# v2_6_Schematic.net
KiCad netlist of a schematic drawn in EAGLE
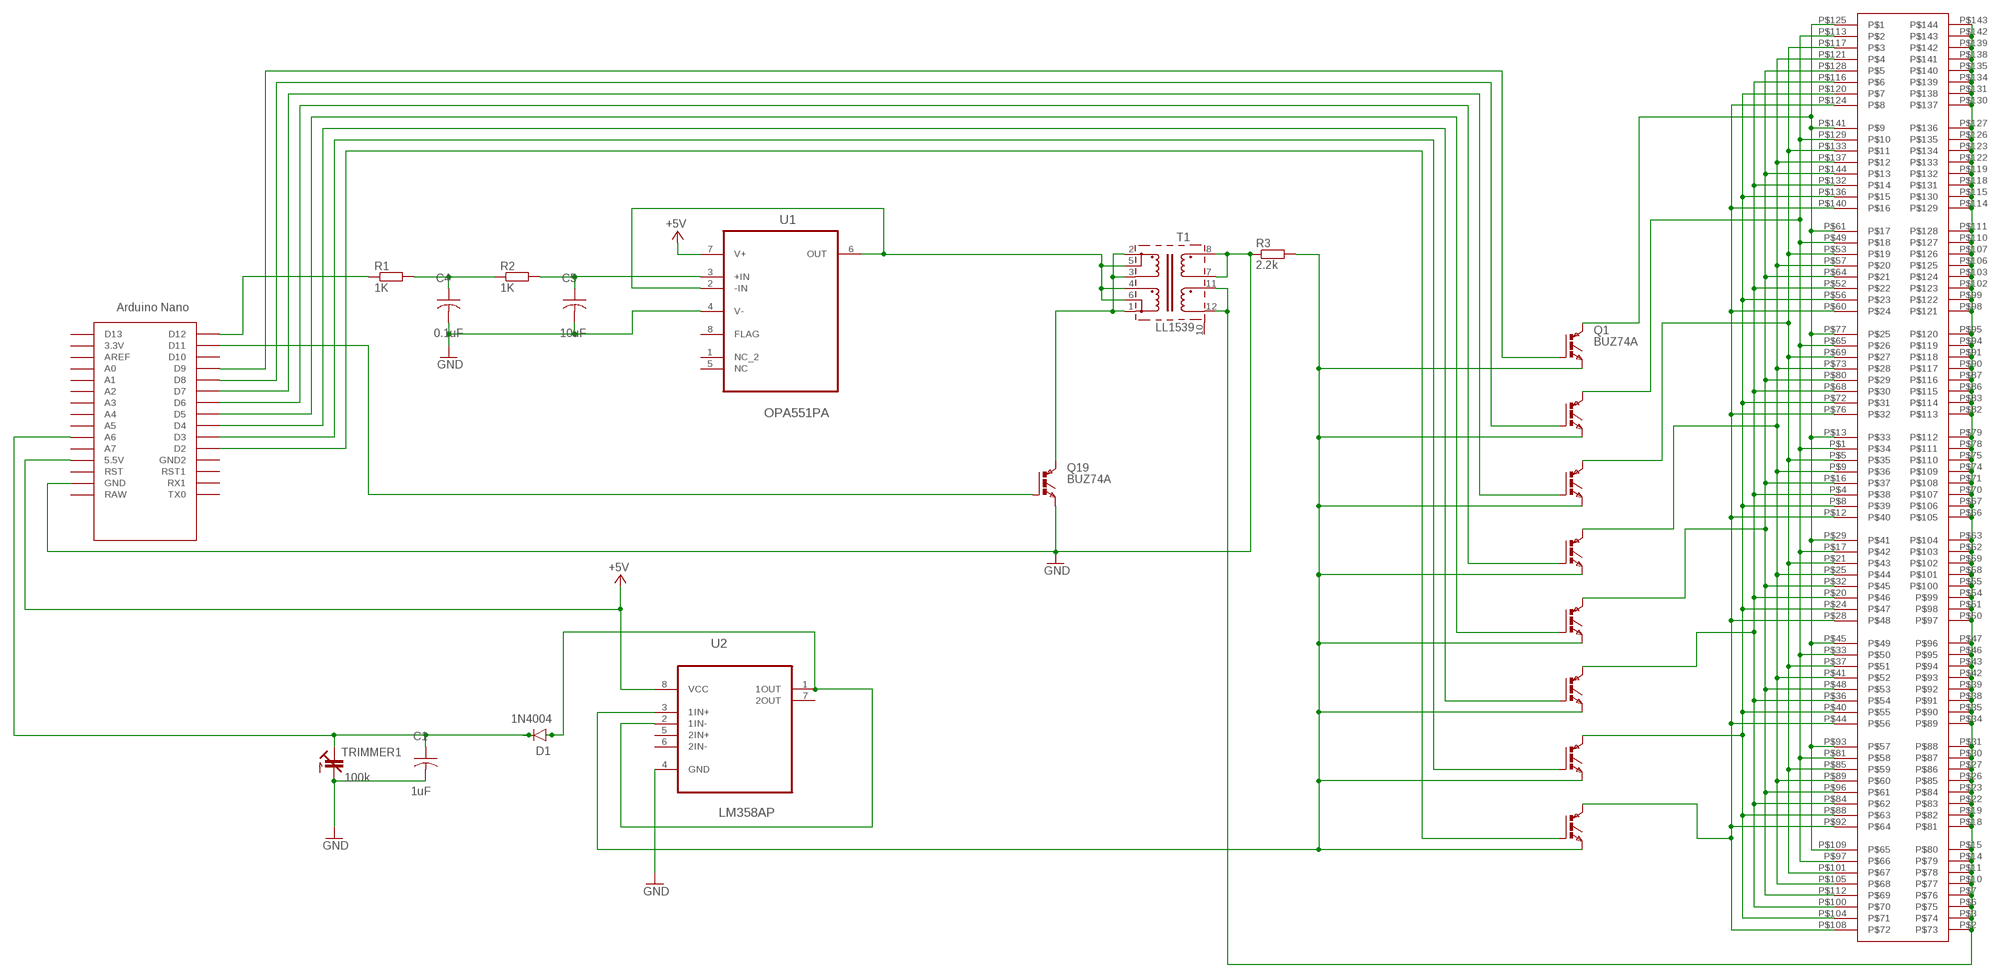
[diagram p0: schematic, sheet 1]

(export (version "E")
  (design (tool "Eeschema 10.0.6"))
  (components
    (comp (ref "C1")
      (value "1uF")
      (footprint "eagle-import:CAP_RADIAL_2MM")
      (fields
        (field (name "DIGIKEY_PART_NUMBER") "P5178-ND")
        (field (name "MANUFACTURER") "Panasonic Electronic Components")
        (field (name "MPN") "ECA-1HM100")
        (field (name "CREATED_BY") "PCBLayout.com")
      )
      (libsource (lib "eagle-import") (part "ECA-1HM100"))
    )
    (comp (ref "C4")
      (value "0.1uF")
      (footprint "eagle-import:CAP_RADIAL_2MM")
      (fields
        (field (name "DIGIKEY_PART_NUMBER") "P5178-ND")
        (field (name "MANUFACTURER") "Panasonic Electronic Components")
        (field (name "MPN") "ECA-1HM100")
        (field (name "CREATED_BY") "PCBLayout.com")
      )
      (libsource (lib "eagle-import") (part "ECA-1HM100"))
    )
    (comp (ref "C5")
      (value "10uF")
      (footprint "eagle-import:CAP_RADIAL_2MM")
      (fields
        (field (name "DIGIKEY_PART_NUMBER") "P5178-ND")
        (field (name "MANUFACTURER") "Panasonic Electronic Components")
        (field (name "MPN") "ECA-1HM100")
        (field (name "CREATED_BY") "PCBLayout.com")
      )
      (libsource (lib "eagle-import") (part "ECA-1HM100"))
    )
    (comp (ref "D1")
      (value "1N4004")
      (footprint "eagle-import:DO-41")
      (fields
        (field (name "DIGIKEY_PART_NUMBER") "1N4004MSCT-ND")
        (field (name "MANUFACTURER") "Micro Commercial Co")
        (field (name "CREATED_BY") "PCBLayout.com")
      )
      (libsource (lib "eagle-import") (part "1N4004"))
    )
    (comp (ref "Q1")
      (value "BUZ74A")
      (footprint "eagle-import:TO220AV")
      (libsource (lib "eagle-import") (part "IGBTTO220AV"))
    )
    (comp (ref "Q2")
      (value "BUZ74A")
      (footprint "eagle-import:TO220AV")
      (libsource (lib "eagle-import") (part "IGBTTO220AV"))
    )
    (comp (ref "Q3")
      (value "BUZ74A")
      (footprint "eagle-import:TO220AV")
      (libsource (lib "eagle-import") (part "IGBTTO220AV"))
    )
    (comp (ref "Q4")
      (value "BUZ74A")
      (footprint "eagle-import:TO220AV")
      (libsource (lib "eagle-import") (part "IGBTTO220AV"))
    )
    (comp (ref "Q5")
      (value "BUZ74A")
      (footprint "eagle-import:TO220AV")
      (libsource (lib "eagle-import") (part "IGBTTO220AV"))
    )
    (comp (ref "Q6")
      (value "BUZ74A")
      (footprint "eagle-import:TO220AV")
      (libsource (lib "eagle-import") (part "IGBTTO220AV"))
    )
    (comp (ref "Q7")
      (value "BUZ74A")
      (footprint "eagle-import:TO220AV")
      (libsource (lib "eagle-import") (part "IGBTTO220AV"))
    )
    (comp (ref "Q8")
      (value "BUZ74A")
      (footprint "eagle-import:TO220AV")
      (libsource (lib "eagle-import") (part "IGBTTO220AV"))
    )
    (comp (ref "Q19")
      (value "BUZ74A")
      (footprint "eagle-import:TO220AV")
      (libsource (lib "eagle-import") (part "IGBTTO220AV"))
    )
    (comp (ref "R1")
      (value "1K")
      (footprint "eagle-import:0204V")
      (libsource (lib "eagle-import") (part "R-EU_0204/2V"))
    )
    (comp (ref "R2")
      (value "1K")
      (footprint "eagle-import:0204V")
      (libsource (lib "eagle-import") (part "R-EU_0204/2V"))
    )
    (comp (ref "R3")
      (value "2.2k")
      (footprint "eagle-import:0204V")
      (libsource (lib "eagle-import") (part "R-EU_0204/2V"))
    )
    (comp (ref "T1")
      (value "LL1539")
      (footprint "eagle-import:LL1539")
      (libsource (lib "eagle-import") (part "LL1539"))
    )
    (comp (ref "TRIMMER1")
      (value "100k")
      (footprint "eagle-import:CTRIM3040.452")
      (libsource (lib "eagle-import") (part "C-TRIMM3040.452"))
    )
    (comp (ref "U$1")
      (value "NANO")
      (footprint "eagle-import:NANO")
      (libsource (lib "eagle-import") (part "NANO"))
    )
    (comp (ref "U$2")
      (value "DOTS_V2")
      (footprint "eagle-import:DOTS_V2")
      (libsource (lib "eagle-import") (part "DOTS_V2"))
    )
    (comp (ref "U1")
      (value "OPA551PA")
      (footprint "eagle-import:DIP254P762X508-8")
      (libsource (lib "eagle-import") (part "OPA551PA"))
    )
    (comp (ref "U2")
      (value "LM358AP")
      (footprint "eagle-import:DIP254P762X508-8")
      (libsource (lib "eagle-import") (part "LM358AP"))
    )
  )
  (nets
    (net (code "1") (name "+5V") (class "Default")
      (node (ref "U$1") (pin "5V") (pinfunction "5.5V_5V") (pintype "bidirectional"))
      (node (ref "U1") (pin "7") (pinfunction "V+_7") (pintype "power_in"))
      (node (ref "U2") (pin "8") (pinfunction "VCC_8") (pintype "power_in"))
    )
    (net (code "2") (name "GND") (class "Default")
      (node (ref "C1") (pin "2") (pinfunction "2_2") (pintype "passive"))
      (node (ref "C4") (pin "2") (pinfunction "2_2") (pintype "passive"))
      (node (ref "C5") (pin "2") (pinfunction "2_2") (pintype "passive"))
      (node (ref "Q19") (pin "E") (pinfunction "E_E") (pintype "passive"))
      (node (ref "R3") (pin "1") (pinfunction "1_1") (pintype "passive"))
      (node (ref "T1") (pin "7") (pinfunction "7_7") (pintype "passive"))
      (node (ref "T1") (pin "8") (pinfunction "8_8") (pintype "passive"))
      (node (ref "TRIMMER1") (pin "2") (pinfunction "A_2") (pintype "passive"))
      (node (ref "U$1") (pin "GND") (pinfunction "GND_GND") (pintype "bidirectional"))
      (node (ref "U1") (pin "4") (pinfunction "V-_4") (pintype "power_in"))
      (node (ref "U2") (pin "4") (pinfunction "GND_4") (pintype "passive"))
    )
    (net (code "3") (name "Net-(C4-Pad1)") (class "Default")
      (node (ref "C4") (pin "1") (pinfunction "1_1") (pintype "passive"))
      (node (ref "R1") (pin "2") (pinfunction "2_2") (pintype "passive"))
      (node (ref "R2") (pin "1") (pinfunction "1_1") (pintype "passive"))
    )
    (net (code "4") (name "Net-(Q1-PadG)") (class "Default")
      (node (ref "Q1") (pin "G") (pinfunction "G_G") (pintype "passive"))
      (node (ref "U$1") (pin "D9") (pinfunction "D9_D9") (pintype "bidirectional"))
    )
    (net (code "5") (name "Net-(Q2-PadG)") (class "Default")
      (node (ref "Q2") (pin "G") (pinfunction "G_G") (pintype "passive"))
      (node (ref "U$1") (pin "D8") (pinfunction "D8_D8") (pintype "bidirectional"))
    )
    (net (code "6") (name "Net-(Q3-PadG)") (class "Default")
      (node (ref "Q3") (pin "G") (pinfunction "G_G") (pintype "passive"))
      (node (ref "U$1") (pin "D7") (pinfunction "D7_D7") (pintype "bidirectional"))
    )
    (net (code "7") (name "Net-(Q4-PadG)") (class "Default")
      (node (ref "Q4") (pin "G") (pinfunction "G_G") (pintype "passive"))
      (node (ref "U$1") (pin "D6") (pinfunction "D6_D6") (pintype "bidirectional"))
    )
    (net (code "8") (name "Net-(Q5-PadG)") (class "Default")
      (node (ref "Q5") (pin "G") (pinfunction "G_G") (pintype "passive"))
      (node (ref "U$1") (pin "D5") (pinfunction "D5_D5") (pintype "bidirectional"))
    )
    (net (code "9") (name "Net-(Q6-PadG)") (class "Default")
      (node (ref "Q6") (pin "G") (pinfunction "G_G") (pintype "passive"))
      (node (ref "U$1") (pin "D4") (pinfunction "D4_D4") (pintype "bidirectional"))
    )
    (net (code "10") (name "Net-(Q7-PadG)") (class "Default")
      (node (ref "Q7") (pin "G") (pinfunction "G_G") (pintype "passive"))
      (node (ref "U$1") (pin "D3") (pinfunction "D3_D3") (pintype "bidirectional"))
    )
    (net (code "11") (name "Net-(Q8-PadG)") (class "Default")
      (node (ref "Q8") (pin "G") (pinfunction "G_G") (pintype "passive"))
      (node (ref "U$1") (pin "D2") (pinfunction "D2_D2") (pintype "bidirectional"))
    )
    (net (code "12") (name "Net-(Q19-PadC)") (class "Default")
      (node (ref "Q19") (pin "C") (pinfunction "C_C") (pintype "passive"))
      (node (ref "T1") (pin "1") (pinfunction "1_1") (pintype "passive"))
      (node (ref "T1") (pin "2") (pinfunction "2_2") (pintype "passive"))
      (node (ref "T1") (pin "3") (pinfunction "3_3") (pintype "passive"))
    )
    (net (code "13") (name "Net-(Q19-PadG)") (class "Default")
      (node (ref "Q19") (pin "G") (pinfunction "G_G") (pintype "passive"))
      (node (ref "U$1") (pin "D11") (pinfunction "D11_D11") (pintype "bidirectional"))
    )
    (net (code "14") (name "Net-(R1-Pad1)") (class "Default")
      (node (ref "R1") (pin "1") (pinfunction "1_1") (pintype "passive"))
      (node (ref "U$1") (pin "D12") (pinfunction "D12_D12") (pintype "bidirectional"))
    )
    (net (code "15") (name "Net-(TRIMMER1-E)") (class "Default")
      (node (ref "C1") (pin "1") (pinfunction "1_1") (pintype "passive"))
      (node (ref "D1") (pin "C") (pinfunction "C_C") (pintype "passive"))
      (node (ref "TRIMMER1") (pin "1A") (pinfunction "E_1A") (pintype "passive"))
      (node (ref "U$1") (pin "A6") (pinfunction "A6_A6") (pintype "bidirectional"))
    )
    (net (code "16") (name "Net-(U$2-P$1)") (class "Default")
      (node (ref "Q1") (pin "C") (pinfunction "C_C") (pintype "passive"))
      (node (ref "U$2") (pin "P$109") (pinfunction "P$65_P$109") (pintype "output"))
      (node (ref "U$2") (pin "P$125") (pinfunction "P$1_P$125") (pintype "output"))
      (node (ref "U$2") (pin "P$13") (pinfunction "P$33_P$13") (pintype "output"))
      (node (ref "U$2") (pin "P$141") (pinfunction "P$9_P$141") (pintype "output"))
      (node (ref "U$2") (pin "P$29") (pinfunction "P$41_P$29") (pintype "output"))
      (node (ref "U$2") (pin "P$45") (pinfunction "P$49_P$45") (pintype "output"))
      (node (ref "U$2") (pin "P$61") (pinfunction "P$17_P$61") (pintype "output"))
      (node (ref "U$2") (pin "P$77") (pinfunction "P$25_P$77") (pintype "output"))
      (node (ref "U$2") (pin "P$93") (pinfunction "P$57_P$93") (pintype "output"))
    )
    (net (code "17") (name "Net-(U$2-P$10)") (class "Default")
      (node (ref "Q2") (pin "C") (pinfunction "C_C") (pintype "passive"))
      (node (ref "U$2") (pin "P$1") (pinfunction "P$34_P$1") (pintype "output"))
      (node (ref "U$2") (pin "P$113") (pinfunction "P$2_P$113") (pintype "output"))
      (node (ref "U$2") (pin "P$129") (pinfunction "P$10_P$129") (pintype "output"))
      (node (ref "U$2") (pin "P$17") (pinfunction "P$42_P$17") (pintype "output"))
      (node (ref "U$2") (pin "P$33") (pinfunction "P$50_P$33") (pintype "output"))
      (node (ref "U$2") (pin "P$49") (pinfunction "P$18_P$49") (pintype "output"))
      (node (ref "U$2") (pin "P$65") (pinfunction "P$26_P$65") (pintype "output"))
      (node (ref "U$2") (pin "P$81") (pinfunction "P$58_P$81") (pintype "output"))
      (node (ref "U$2") (pin "P$97") (pinfunction "P$66_P$97") (pintype "output"))
    )
    (net (code "18") (name "Net-(U$2-P$11)") (class "Default")
      (node (ref "Q3") (pin "C") (pinfunction "C_C") (pintype "passive"))
      (node (ref "U$2") (pin "P$101") (pinfunction "P$67_P$101") (pintype "output"))
      (node (ref "U$2") (pin "P$117") (pinfunction "P$3_P$117") (pintype "output"))
      (node (ref "U$2") (pin "P$133") (pinfunction "P$11_P$133") (pintype "output"))
      (node (ref "U$2") (pin "P$21") (pinfunction "P$43_P$21") (pintype "output"))
      (node (ref "U$2") (pin "P$37") (pinfunction "P$51_P$37") (pintype "output"))
      (node (ref "U$2") (pin "P$5") (pinfunction "P$35_P$5") (pintype "output"))
      (node (ref "U$2") (pin "P$53") (pinfunction "P$19_P$53") (pintype "output"))
      (node (ref "U$2") (pin "P$69") (pinfunction "P$27_P$69") (pintype "output"))
      (node (ref "U$2") (pin "P$85") (pinfunction "P$59_P$85") (pintype "output"))
    )
    (net (code "19") (name "Net-(U$2-P$12)") (class "Default")
      (node (ref "Q4") (pin "C") (pinfunction "C_C") (pintype "passive"))
      (node (ref "U$2") (pin "P$105") (pinfunction "P$68_P$105") (pintype "output"))
      (node (ref "U$2") (pin "P$121") (pinfunction "P$4_P$121") (pintype "output"))
      (node (ref "U$2") (pin "P$137") (pinfunction "P$12_P$137") (pintype "output"))
      (node (ref "U$2") (pin "P$25") (pinfunction "P$44_P$25") (pintype "output"))
      (node (ref "U$2") (pin "P$41") (pinfunction "P$52_P$41") (pintype "output"))
      (node (ref "U$2") (pin "P$57") (pinfunction "P$20_P$57") (pintype "output"))
      (node (ref "U$2") (pin "P$73") (pinfunction "P$28_P$73") (pintype "output"))
      (node (ref "U$2") (pin "P$89") (pinfunction "P$60_P$89") (pintype "output"))
      (node (ref "U$2") (pin "P$9") (pinfunction "P$36_P$9") (pintype "output"))
    )
    (net (code "20") (name "Net-(U$2-P$13)") (class "Default")
      (node (ref "Q5") (pin "C") (pinfunction "C_C") (pintype "passive"))
      (node (ref "U$2") (pin "P$112") (pinfunction "P$69_P$112") (pintype "output"))
      (node (ref "U$2") (pin "P$128") (pinfunction "P$5_P$128") (pintype "output"))
      (node (ref "U$2") (pin "P$144") (pinfunction "P$13_P$144") (pintype "output"))
      (node (ref "U$2") (pin "P$16") (pinfunction "P$37_P$16") (pintype "output"))
      (node (ref "U$2") (pin "P$32") (pinfunction "P$45_P$32") (pintype "output"))
      (node (ref "U$2") (pin "P$48") (pinfunction "P$53_P$48") (pintype "output"))
      (node (ref "U$2") (pin "P$64") (pinfunction "P$21_P$64") (pintype "output"))
      (node (ref "U$2") (pin "P$80") (pinfunction "P$29_P$80") (pintype "output"))
      (node (ref "U$2") (pin "P$96") (pinfunction "P$61_P$96") (pintype "output"))
    )
    (net (code "21") (name "Net-(U$2-P$14)") (class "Default")
      (node (ref "Q6") (pin "C") (pinfunction "C_C") (pintype "passive"))
      (node (ref "U$2") (pin "P$100") (pinfunction "P$70_P$100") (pintype "output"))
      (node (ref "U$2") (pin "P$116") (pinfunction "P$6_P$116") (pintype "output"))
      (node (ref "U$2") (pin "P$132") (pinfunction "P$14_P$132") (pintype "output"))
      (node (ref "U$2") (pin "P$20") (pinfunction "P$46_P$20") (pintype "output"))
      (node (ref "U$2") (pin "P$36") (pinfunction "P$54_P$36") (pintype "output"))
      (node (ref "U$2") (pin "P$4") (pinfunction "P$38_P$4") (pintype "output"))
      (node (ref "U$2") (pin "P$52") (pinfunction "P$22_P$52") (pintype "output"))
      (node (ref "U$2") (pin "P$68") (pinfunction "P$30_P$68") (pintype "output"))
      (node (ref "U$2") (pin "P$84") (pinfunction "P$62_P$84") (pintype "output"))
    )
    (net (code "22") (name "Net-(U$2-P$15)") (class "Default")
      (node (ref "Q7") (pin "C") (pinfunction "C_C") (pintype "passive"))
      (node (ref "U$2") (pin "P$104") (pinfunction "P$71_P$104") (pintype "output"))
      (node (ref "U$2") (pin "P$120") (pinfunction "P$7_P$120") (pintype "output"))
      (node (ref "U$2") (pin "P$136") (pinfunction "P$15_P$136") (pintype "output"))
      (node (ref "U$2") (pin "P$24") (pinfunction "P$47_P$24") (pintype "output"))
      (node (ref "U$2") (pin "P$40") (pinfunction "P$55_P$40") (pintype "output"))
      (node (ref "U$2") (pin "P$56") (pinfunction "P$23_P$56") (pintype "output"))
      (node (ref "U$2") (pin "P$72") (pinfunction "P$31_P$72") (pintype "output"))
      (node (ref "U$2") (pin "P$8") (pinfunction "P$39_P$8") (pintype "output"))
      (node (ref "U$2") (pin "P$88") (pinfunction "P$63_P$88") (pintype "output"))
    )
    (net (code "23") (name "Net-(U$2-P$16)") (class "Default")
      (node (ref "Q8") (pin "C") (pinfunction "C_C") (pintype "passive"))
      (node (ref "U$2") (pin "P$108") (pinfunction "P$72_P$108") (pintype "output"))
      (node (ref "U$2") (pin "P$12") (pinfunction "P$40_P$12") (pintype "output"))
      (node (ref "U$2") (pin "P$124") (pinfunction "P$8_P$124") (pintype "output"))
      (node (ref "U$2") (pin "P$140") (pinfunction "P$16_P$140") (pintype "output"))
      (node (ref "U$2") (pin "P$28") (pinfunction "P$48_P$28") (pintype "output"))
      (node (ref "U$2") (pin "P$44") (pinfunction "P$56_P$44") (pintype "output"))
      (node (ref "U$2") (pin "P$60") (pinfunction "P$24_P$60") (pintype "output"))
      (node (ref "U$2") (pin "P$76") (pinfunction "P$32_P$76") (pintype "output"))
      (node (ref "U$2") (pin "P$92") (pinfunction "P$64_P$92") (pintype "output"))
    )
    (net (code "24") (name "Net-(U$2-P$100)") (class "Default")
      (node (ref "T1") (pin "11") (pinfunction "11_11") (pintype "passive"))
      (node (ref "T1") (pin "12") (pinfunction "12_12") (pintype "passive"))
      (node (ref "U$2") (pin "P$10") (pinfunction "P$77_P$10") (pintype "power_in"))
      (node (ref "U$2") (pin "P$102") (pinfunction "P$123_P$102") (pintype "power_in"))
      (node (ref "U$2") (pin "P$103") (pinfunction "P$124_P$103") (pintype "power_in"))
      (node (ref "U$2") (pin "P$106") (pinfunction "P$125_P$106") (pintype "power_in"))
      (node (ref "U$2") (pin "P$107") (pinfunction "P$126_P$107") (pintype "power_in"))
      (node (ref "U$2") (pin "P$11") (pinfunction "P$78_P$11") (pintype "power_in"))
      (node (ref "U$2") (pin "P$110") (pinfunction "P$127_P$110") (pintype "power_in"))
      (node (ref "U$2") (pin "P$111") (pinfunction "P$128_P$111") (pintype "power_in"))
      (node (ref "U$2") (pin "P$114") (pinfunction "P$129_P$114") (pintype "power_in"))
      (node (ref "U$2") (pin "P$115") (pinfunction "P$130_P$115") (pintype "power_in"))
      (node (ref "U$2") (pin "P$118") (pinfunction "P$131_P$118") (pintype "power_in"))
      (node (ref "U$2") (pin "P$119") (pinfunction "P$132_P$119") (pintype "power_in"))
      (node (ref "U$2") (pin "P$122") (pinfunction "P$133_P$122") (pintype "power_in"))
      (node (ref "U$2") (pin "P$123") (pinfunction "P$134_P$123") (pintype "power_in"))
      (node (ref "U$2") (pin "P$126") (pinfunction "P$135_P$126") (pintype "power_in"))
      (node (ref "U$2") (pin "P$127") (pinfunction "P$136_P$127") (pintype "power_in"))
      (node (ref "U$2") (pin "P$130") (pinfunction "P$137_P$130") (pintype "power_in"))
      (node (ref "U$2") (pin "P$131") (pinfunction "P$138_P$131") (pintype "power_in"))
      (node (ref "U$2") (pin "P$134") (pinfunction "P$139_P$134") (pintype "power_in"))
      (node (ref "U$2") (pin "P$135") (pinfunction "P$140_P$135") (pintype "power_in"))
      (node (ref "U$2") (pin "P$138") (pinfunction "P$141_P$138") (pintype "power_in"))
      (node (ref "U$2") (pin "P$139") (pinfunction "P$142_P$139") (pintype "power_in"))
      (node (ref "U$2") (pin "P$14") (pinfunction "P$79_P$14") (pintype "power_in"))
      (node (ref "U$2") (pin "P$142") (pinfunction "P$143_P$142") (pintype "power_in"))
      (node (ref "U$2") (pin "P$143") (pinfunction "P$144_P$143") (pintype "power_in"))
      (node (ref "U$2") (pin "P$15") (pinfunction "P$80_P$15") (pintype "power_in"))
      (node (ref "U$2") (pin "P$18") (pinfunction "P$81_P$18") (pintype "power_in"))
      (node (ref "U$2") (pin "P$19") (pinfunction "P$82_P$19") (pintype "power_in"))
      (node (ref "U$2") (pin "P$2") (pinfunction "P$73_P$2") (pintype "power_in"))
      (node (ref "U$2") (pin "P$22") (pinfunction "P$83_P$22") (pintype "power_in"))
      (node (ref "U$2") (pin "P$23") (pinfunction "P$84_P$23") (pintype "power_in"))
      (node (ref "U$2") (pin "P$26") (pinfunction "P$85_P$26") (pintype "power_in"))
      (node (ref "U$2") (pin "P$27") (pinfunction "P$86_P$27") (pintype "power_in"))
      (node (ref "U$2") (pin "P$3") (pinfunction "P$74_P$3") (pintype "power_in"))
      (node (ref "U$2") (pin "P$30") (pinfunction "P$87_P$30") (pintype "power_in"))
      (node (ref "U$2") (pin "P$31") (pinfunction "P$88_P$31") (pintype "power_in"))
      (node (ref "U$2") (pin "P$34") (pinfunction "P$89_P$34") (pintype "power_in"))
      (node (ref "U$2") (pin "P$35") (pinfunction "P$90_P$35") (pintype "power_in"))
      (node (ref "U$2") (pin "P$38") (pinfunction "P$91_P$38") (pintype "power_in"))
      (node (ref "U$2") (pin "P$39") (pinfunction "P$92_P$39") (pintype "power_in"))
      (node (ref "U$2") (pin "P$42") (pinfunction "P$93_P$42") (pintype "power_in"))
      (node (ref "U$2") (pin "P$43") (pinfunction "P$94_P$43") (pintype "power_in"))
      (node (ref "U$2") (pin "P$46") (pinfunction "P$95_P$46") (pintype "power_in"))
      (node (ref "U$2") (pin "P$47") (pinfunction "P$96_P$47") (pintype "power_in"))
      (node (ref "U$2") (pin "P$50") (pinfunction "P$97_P$50") (pintype "power_in"))
      (node (ref "U$2") (pin "P$51") (pinfunction "P$98_P$51") (pintype "power_in"))
      (node (ref "U$2") (pin "P$54") (pinfunction "P$99_P$54") (pintype "power_in"))
      (node (ref "U$2") (pin "P$55") (pinfunction "P$100_P$55") (pintype "power_in"))
      (node (ref "U$2") (pin "P$58") (pinfunction "P$101_P$58") (pintype "power_in"))
      (node (ref "U$2") (pin "P$59") (pinfunction "P$102_P$59") (pintype "power_in"))
      (node (ref "U$2") (pin "P$6") (pinfunction "P$75_P$6") (pintype "power_in"))
      (node (ref "U$2") (pin "P$62") (pinfunction "P$103_P$62") (pintype "power_in"))
      (node (ref "U$2") (pin "P$63") (pinfunction "P$104_P$63") (pintype "power_in"))
      (node (ref "U$2") (pin "P$66") (pinfunction "P$105_P$66") (pintype "power_in"))
      (node (ref "U$2") (pin "P$67") (pinfunction "P$106_P$67") (pintype "power_in"))
      (node (ref "U$2") (pin "P$7") (pinfunction "P$76_P$7") (pintype "power_in"))
      (node (ref "U$2") (pin "P$70") (pinfunction "P$107_P$70") (pintype "power_in"))
      (node (ref "U$2") (pin "P$71") (pinfunction "P$108_P$71") (pintype "power_in"))
      (node (ref "U$2") (pin "P$74") (pinfunction "P$109_P$74") (pintype "power_in"))
      (node (ref "U$2") (pin "P$75") (pinfunction "P$110_P$75") (pintype "power_in"))
      (node (ref "U$2") (pin "P$78") (pinfunction "P$111_P$78") (pintype "power_in"))
      (node (ref "U$2") (pin "P$79") (pinfunction "P$112_P$79") (pintype "power_in"))
      (node (ref "U$2") (pin "P$82") (pinfunction "P$113_P$82") (pintype "power_in"))
      (node (ref "U$2") (pin "P$83") (pinfunction "P$114_P$83") (pintype "power_in"))
      (node (ref "U$2") (pin "P$86") (pinfunction "P$115_P$86") (pintype "power_in"))
      (node (ref "U$2") (pin "P$87") (pinfunction "P$116_P$87") (pintype "power_in"))
      (node (ref "U$2") (pin "P$90") (pinfunction "P$117_P$90") (pintype "power_in"))
      (node (ref "U$2") (pin "P$91") (pinfunction "P$118_P$91") (pintype "power_in"))
      (node (ref "U$2") (pin "P$94") (pinfunction "P$119_P$94") (pintype "power_in"))
      (node (ref "U$2") (pin "P$95") (pinfunction "P$120_P$95") (pintype "power_in"))
      (node (ref "U$2") (pin "P$98") (pinfunction "P$121_P$98") (pintype "power_in"))
      (node (ref "U$2") (pin "P$99") (pinfunction "P$122_P$99") (pintype "power_in"))
    )
    (net (code "25") (name "Net-(U1-+IN)") (class "Default")
      (node (ref "C5") (pin "1") (pinfunction "1_1") (pintype "passive"))
      (node (ref "R2") (pin "2") (pinfunction "2_2") (pintype "passive"))
      (node (ref "U1") (pin "3") (pinfunction "+IN_3") (pintype "input"))
    )
    (net (code "26") (name "Net-(U1--IN)") (class "Default")
      (node (ref "T1") (pin "4") (pinfunction "4_4") (pintype "passive"))
      (node (ref "T1") (pin "5") (pinfunction "5_5") (pintype "passive"))
      (node (ref "T1") (pin "6") (pinfunction "6_6") (pintype "passive"))
      (node (ref "U1") (pin "2") (pinfunction "-IN_2") (pintype "input"))
      (node (ref "U1") (pin "6") (pinfunction "OUT_6") (pintype "output"))
    )
    (net (code "27") (name "Net-(U2-1IN+)") (class "Default")
      (node (ref "Q1") (pin "E") (pinfunction "E_E") (pintype "passive"))
      (node (ref "Q2") (pin "E") (pinfunction "E_E") (pintype "passive"))
      (node (ref "Q3") (pin "E") (pinfunction "E_E") (pintype "passive"))
      (node (ref "Q4") (pin "E") (pinfunction "E_E") (pintype "passive"))
      (node (ref "Q5") (pin "E") (pinfunction "E_E") (pintype "passive"))
      (node (ref "Q6") (pin "E") (pinfunction "E_E") (pintype "passive"))
      (node (ref "Q7") (pin "E") (pinfunction "E_E") (pintype "passive"))
      (node (ref "Q8") (pin "E") (pinfunction "E_E") (pintype "passive"))
      (node (ref "R3") (pin "2") (pinfunction "2_2") (pintype "passive"))
      (node (ref "U2") (pin "3") (pinfunction "1IN+_3") (pintype "input"))
    )
    (net (code "28") (name "Net-(U2-1IN-)") (class "Default")
      (node (ref "D1") (pin "A") (pinfunction "A_A") (pintype "passive"))
      (node (ref "U2") (pin "1") (pinfunction "1OUT_1") (pintype "output"))
      (node (ref "U2") (pin "2") (pinfunction "1IN-_2") (pintype "input"))
    )
    (net (code "29") (name "unconnected-(T1-Pad10)") (class "Default")
      (node (ref "T1") (pin "10") (pinfunction "10_10") (pintype "passive"))
    )
    (net (code "30") (name "unconnected-(U$1-GND2-PadGND1)") (class "Default")
      (node (ref "U$1") (pin "GND1") (pinfunction "GND2_GND1") (pintype "bidirectional"))
    )
    (net (code "31") (name "unconnected-(U$1-Pad3.3V)") (class "Default")
      (node (ref "U$1") (pin "3.3V") (pinfunction "3.3V_3.3V") (pintype "bidirectional"))
    )
    (net (code "32") (name "unconnected-(U$1-PadA0)") (class "Default")
      (node (ref "U$1") (pin "A0") (pinfunction "A0_A0") (pintype "bidirectional"))
    )
    (net (code "33") (name "unconnected-(U$1-PadA1)") (class "Default")
      (node (ref "U$1") (pin "A1") (pinfunction "A1_A1") (pintype "bidirectional"))
    )
    (net (code "34") (name "unconnected-(U$1-PadA2)") (class "Default")
      (node (ref "U$1") (pin "A2") (pinfunction "A2_A2") (pintype "bidirectional"))
    )
    (net (code "35") (name "unconnected-(U$1-PadA3)") (class "Default")
      (node (ref "U$1") (pin "A3") (pinfunction "A3_A3") (pintype "bidirectional"))
    )
    (net (code "36") (name "unconnected-(U$1-PadA4)") (class "Default")
      (node (ref "U$1") (pin "A4") (pinfunction "A4_A4") (pintype "bidirectional"))
    )
    (net (code "37") (name "unconnected-(U$1-PadA5)") (class "Default")
      (node (ref "U$1") (pin "A5") (pinfunction "A5_A5") (pintype "bidirectional"))
    )
    (net (code "38") (name "unconnected-(U$1-PadA7)") (class "Default")
      (node (ref "U$1") (pin "A7") (pinfunction "A7_A7") (pintype "bidirectional"))
    )
    (net (code "39") (name "unconnected-(U$1-PadAREF)") (class "Default")
      (node (ref "U$1") (pin "AREF") (pinfunction "AREF_AREF") (pintype "bidirectional"))
    )
    (net (code "40") (name "unconnected-(U$1-PadD10)") (class "Default")
      (node (ref "U$1") (pin "D10") (pinfunction "D10_D10") (pintype "bidirectional"))
    )
    (net (code "41") (name "unconnected-(U$1-PadD13)") (class "Default")
      (node (ref "U$1") (pin "D13") (pinfunction "D13_D13") (pintype "bidirectional"))
    )
    (net (code "42") (name "unconnected-(U$1-PadRAW)") (class "Default")
      (node (ref "U$1") (pin "RAW") (pinfunction "RAW_RAW") (pintype "bidirectional"))
    )
    (net (code "43") (name "unconnected-(U$1-PadRST)") (class "Default")
      (node (ref "U$1") (pin "RST") (pinfunction "RST_RST") (pintype "bidirectional"))
    )
    (net (code "44") (name "unconnected-(U$1-PadRST1)") (class "Default")
      (node (ref "U$1") (pin "RST1") (pinfunction "RST1_RST1") (pintype "bidirectional"))
    )
    (net (code "45") (name "unconnected-(U$1-PadRX1)") (class "Default")
      (node (ref "U$1") (pin "RX1") (pinfunction "RX1_RX1") (pintype "bidirectional"))
    )
    (net (code "46") (name "unconnected-(U$1-PadTX0)") (class "Default")
      (node (ref "U$1") (pin "TX0") (pinfunction "TX0_TX0") (pintype "bidirectional"))
    )
    (net (code "47") (name "unconnected-(U1-FLAG-Pad8)") (class "Default")
      (node (ref "U1") (pin "8") (pinfunction "FLAG_8") (pintype "passive"))
    )
    (net (code "48") (name "unconnected-(U1-NC-Pad5)") (class "Default")
      (node (ref "U1") (pin "5") (pinfunction "NC_5") (pintype "no_connect"))
    )
    (net (code "49") (name "unconnected-(U1-NC_2-Pad1)") (class "Default")
      (node (ref "U1") (pin "1") (pinfunction "NC_2_1") (pintype "no_connect"))
    )
    (net (code "50") (name "unconnected-(U2-2IN+-Pad5)") (class "Default")
      (node (ref "U2") (pin "5") (pinfunction "2IN+_5") (pintype "input"))
    )
    (net (code "51") (name "unconnected-(U2-2IN--Pad6)") (class "Default")
      (node (ref "U2") (pin "6") (pinfunction "2IN-_6") (pintype "input"))
    )
    (net (code "52") (name "unconnected-(U2-2OUT-Pad7)") (class "Default")
      (node (ref "U2") (pin "7") (pinfunction "2OUT_7") (pintype "output"))
    )
  )
)
